# board.net
KiCad netlist of a schematic drawn in EAGLE
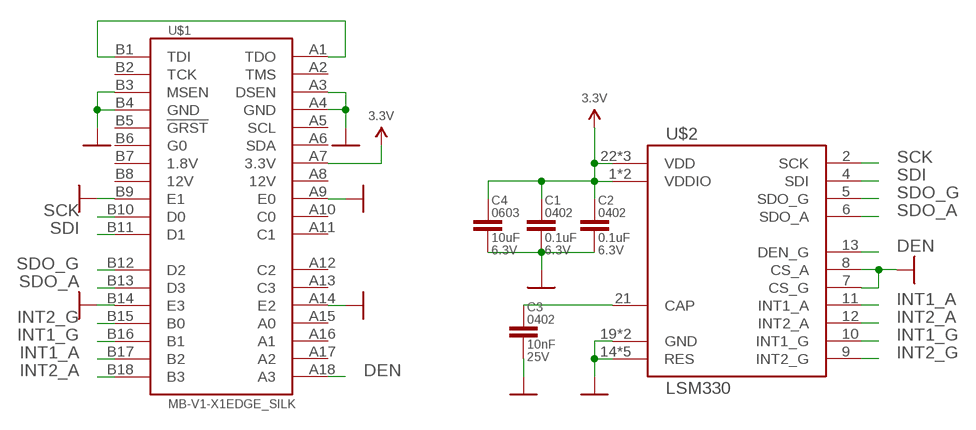
[diagram p0: schematic, sheet 1]

(export (version "E")
  (design (tool "Eeschema 10.0.6"))
  (components
    (comp (ref "C1")
      (value "0.1uF")
      (footprint "eagle-import:0402-CAP")
      (fields (field (name "VOLTAGE") "6.3V"))
      (libsource (lib "eagle-import") (part "CAP0402-CAP"))
    )
    (comp (ref "C2")
      (value "0.1uF")
      (footprint "eagle-import:0402-CAP")
      (fields (field (name "VOLTAGE") "6.3V"))
      (libsource (lib "eagle-import") (part "CAP0402-CAP"))
    )
    (comp (ref "C3")
      (value "10nF")
      (footprint "eagle-import:0402-CAP")
      (fields (field (name "VOLTAGE") "6.3V") (field (name "VOLTAGE_1") "25V"))
      (libsource (lib "eagle-import") (part "CAP0402-CAP"))
    )
    (comp (ref "C4")
      (value "10uF")
      (footprint "eagle-import:0603-CAP")
      (fields (field (name "VOLTAGE") "6.3V"))
      (libsource (lib "eagle-import") (part "CAP0603"))
    )
    (comp (ref "U$1")
      (value "MB-V1-X1EDGE_SILK")
      (footprint "eagle-import:MB-V1-X1-EDGE")
      (libsource (lib "eagle-import") (part "MB-V1-X1EDGE_SILK"))
    )
    (comp (ref "U$2")
      (value "LSM330")
      (footprint "eagle-import:LSM330")
      (libsource (lib "eagle-import") (part "LSM330"))
    )
  )
  (nets
    (net (code "1") (name "/DEN") (class "Default")
      (node (ref "U$1") (pin "A18") (pinfunction "A3_A18") (pintype "bidirectional"))
      (node (ref "U$2") (pin "13") (pinfunction "DEN_G_13") (pintype "input"))
    )
    (net (code "2") (name "/INT1_A") (class "Default")
      (node (ref "U$1") (pin "B17") (pinfunction "B2_B17") (pintype "bidirectional"))
      (node (ref "U$2") (pin "11") (pinfunction "INT1_A_11") (pintype "output"))
    )
    (net (code "3") (name "/INT1_G") (class "Default")
      (node (ref "U$1") (pin "B16") (pinfunction "B1_B16") (pintype "bidirectional"))
      (node (ref "U$2") (pin "10") (pinfunction "INT1_G_10") (pintype "output"))
    )
    (net (code "4") (name "/INT2_A") (class "Default")
      (node (ref "U$1") (pin "B18") (pinfunction "B3_B18") (pintype "bidirectional"))
      (node (ref "U$2") (pin "12") (pinfunction "INT2_A_12") (pintype "output"))
    )
    (net (code "5") (name "/INT2_G") (class "Default")
      (node (ref "U$1") (pin "B15") (pinfunction "B0_B15") (pintype "bidirectional"))
      (node (ref "U$2") (pin "9") (pinfunction "INT2_G_9") (pintype "output"))
    )
    (net (code "6") (name "/SCK") (class "Default")
      (node (ref "U$1") (pin "B10") (pinfunction "D0_B10") (pintype "bidirectional"))
      (node (ref "U$2") (pin "2") (pinfunction "SCK_2") (pintype "bidirectional"))
    )
    (net (code "7") (name "/SDI") (class "Default")
      (node (ref "U$1") (pin "B11") (pinfunction "D1_B11") (pintype "bidirectional"))
      (node (ref "U$2") (pin "4") (pinfunction "SDI_4") (pintype "bidirectional"))
    )
    (net (code "8") (name "/SDO_A") (class "Default")
      (node (ref "U$1") (pin "B13") (pinfunction "D3_B13") (pintype "bidirectional"))
      (node (ref "U$2") (pin "6") (pinfunction "SDO_A_6") (pintype "bidirectional"))
    )
    (net (code "9") (name "/SDO_G") (class "Default")
      (node (ref "U$1") (pin "B12") (pinfunction "D2_B12") (pintype "bidirectional"))
      (node (ref "U$2") (pin "5") (pinfunction "SDO_G_5") (pintype "bidirectional"))
    )
    (net (code "10") (name "3.3V") (class "Default")
      (node (ref "C1") (pin "1") (pinfunction "1_1") (pintype "passive"))
      (node (ref "C2") (pin "1") (pinfunction "1_1") (pintype "passive"))
      (node (ref "C4") (pin "1") (pinfunction "1_1") (pintype "passive"))
      (node (ref "U$1") (pin "A7") (pinfunction "3.3V_A7") (pintype "bidirectional"))
      (node (ref "U$2") (pin "1") (pinfunction "VDDIO_1") (pintype "input"))
      (node (ref "U$2") (pin "22") (pinfunction "VDD_22") (pintype "input"))
      (node (ref "U$2") (pin "23") (pinfunction "VDD_23") (pintype "input"))
      (node (ref "U$2") (pin "24") (pinfunction "VDD_24") (pintype "input"))
      (node (ref "U$2") (pin "3") (pinfunction "VDDIO_3") (pintype "input"))
    )
    (net (code "11") (name "GND") (class "Default")
      (node (ref "C1") (pin "2") (pinfunction "2_2") (pintype "passive"))
      (node (ref "C2") (pin "2") (pinfunction "2_2") (pintype "passive"))
      (node (ref "C3") (pin "2") (pinfunction "2_2") (pintype "passive"))
      (node (ref "C4") (pin "2") (pinfunction "2_2") (pintype "passive"))
      (node (ref "U$1") (pin "A14") (pinfunction "E2_A14") (pintype "bidirectional"))
      (node (ref "U$1") (pin "A3") (pinfunction "DSEN_A3") (pintype "bidirectional"))
      (node (ref "U$1") (pin "A4") (pinfunction "GND_A4") (pintype "input"))
      (node (ref "U$1") (pin "A9") (pinfunction "E0_A9") (pintype "bidirectional"))
      (node (ref "U$1") (pin "B14") (pinfunction "E3_B14") (pintype "bidirectional"))
      (node (ref "U$1") (pin "B3") (pinfunction "MSEN_B3") (pintype "bidirectional"))
      (node (ref "U$1") (pin "B4") (pinfunction "GND_B4") (pintype "input"))
      (node (ref "U$1") (pin "B9") (pinfunction "E1_B9") (pintype "bidirectional"))
      (node (ref "U$2") (pin "14") (pinfunction "RES_14") (pintype "input"))
      (node (ref "U$2") (pin "15") (pinfunction "RES_15") (pintype "input"))
      (node (ref "U$2") (pin "16") (pinfunction "RES_16") (pintype "input"))
      (node (ref "U$2") (pin "17") (pinfunction "RES_17") (pintype "input"))
      (node (ref "U$2") (pin "18") (pinfunction "RES_18") (pintype "input"))
      (node (ref "U$2") (pin "19") (pinfunction "GND_19") (pintype "input"))
      (node (ref "U$2") (pin "20") (pinfunction "GND_20") (pintype "input"))
      (node (ref "U$2") (pin "7") (pinfunction "CS_G_7") (pintype "input"))
      (node (ref "U$2") (pin "8") (pinfunction "CS_A_8") (pintype "input"))
    )
    (net (code "12") (name "Net-(U$1-TDI)") (class "Default")
      (node (ref "U$1") (pin "A1") (pinfunction "TDO_A1") (pintype "input"))
      (node (ref "U$1") (pin "B1") (pinfunction "TDI_B1") (pintype "output"))
    )
    (net (code "13") (name "Net-(U$2-CAP)") (class "Default")
      (node (ref "C3") (pin "1") (pinfunction "1_1") (pintype "passive"))
      (node (ref "U$2") (pin "21") (pinfunction "CAP_21") (pintype "input"))
    )
    (net (code "14") (name "unconnected-(U$1-1.8V-PadB7)") (class "Default")
      (node (ref "U$1") (pin "B7") (pinfunction "1.8V_B7") (pintype "bidirectional"))
    )
    (net (code "15") (name "unconnected-(U$1-12V-PadA8)") (class "Default")
      (node (ref "U$1") (pin "A8") (pinfunction "12V_A8") (pintype "bidirectional"))
    )
    (net (code "16") (name "unconnected-(U$1-12V-PadB8)") (class "Default")
      (node (ref "U$1") (pin "B8") (pinfunction "12V_B8") (pintype "bidirectional"))
    )
    (net (code "17") (name "unconnected-(U$1-A0-PadA15)") (class "Default")
      (node (ref "U$1") (pin "A15") (pinfunction "A0_A15") (pintype "bidirectional"))
    )
    (net (code "18") (name "unconnected-(U$1-A1-PadA16)") (class "Default")
      (node (ref "U$1") (pin "A16") (pinfunction "A1_A16") (pintype "bidirectional"))
    )
    (net (code "19") (name "unconnected-(U$1-A2-PadA17)") (class "Default")
      (node (ref "U$1") (pin "A17") (pinfunction "A2_A17") (pintype "bidirectional"))
    )
    (net (code "20") (name "unconnected-(U$1-C0-PadA10)") (class "Default")
      (node (ref "U$1") (pin "A10") (pinfunction "C0_A10") (pintype "bidirectional"))
    )
    (net (code "21") (name "unconnected-(U$1-C1-PadA11)") (class "Default")
      (node (ref "U$1") (pin "A11") (pinfunction "C1_A11") (pintype "bidirectional"))
    )
    (net (code "22") (name "unconnected-(U$1-C2-PadA12)") (class "Default")
      (node (ref "U$1") (pin "A12") (pinfunction "C2_A12") (pintype "bidirectional"))
    )
    (net (code "23") (name "unconnected-(U$1-C3-PadA13)") (class "Default")
      (node (ref "U$1") (pin "A13") (pinfunction "C3_A13") (pintype "bidirectional"))
    )
    (net (code "24") (name "unconnected-(U$1-G0-PadB6)") (class "Default")
      (node (ref "U$1") (pin "B6") (pinfunction "G0_B6") (pintype "bidirectional"))
    )
    (net (code "25") (name "unconnected-(U$1-SCL-PadA5)") (class "Default")
      (node (ref "U$1") (pin "A5") (pinfunction "SCL_A5") (pintype "bidirectional"))
    )
    (net (code "26") (name "unconnected-(U$1-SDA-PadA6)") (class "Default")
      (node (ref "U$1") (pin "A6") (pinfunction "SDA_A6") (pintype "bidirectional"))
    )
    (net (code "27") (name "unconnected-(U$1-TCK-PadB2)") (class "Default")
      (node (ref "U$1") (pin "B2") (pinfunction "TCK_B2") (pintype "bidirectional"))
    )
    (net (code "28") (name "unconnected-(U$1-TMS-PadA2)") (class "Default")
      (node (ref "U$1") (pin "A2") (pinfunction "TMS_A2") (pintype "bidirectional"))
    )
    (net (code "29") (name "unconnected-(U$1-~{GRST}-PadB5)") (class "Default")
      (node (ref "U$1") (pin "B5") (pinfunction "~{GRST}_B5") (pintype "bidirectional"))
    )
  )
)
